# LowduinoPTH_Take2.net
KiCad netlist of a schematic drawn in EAGLE
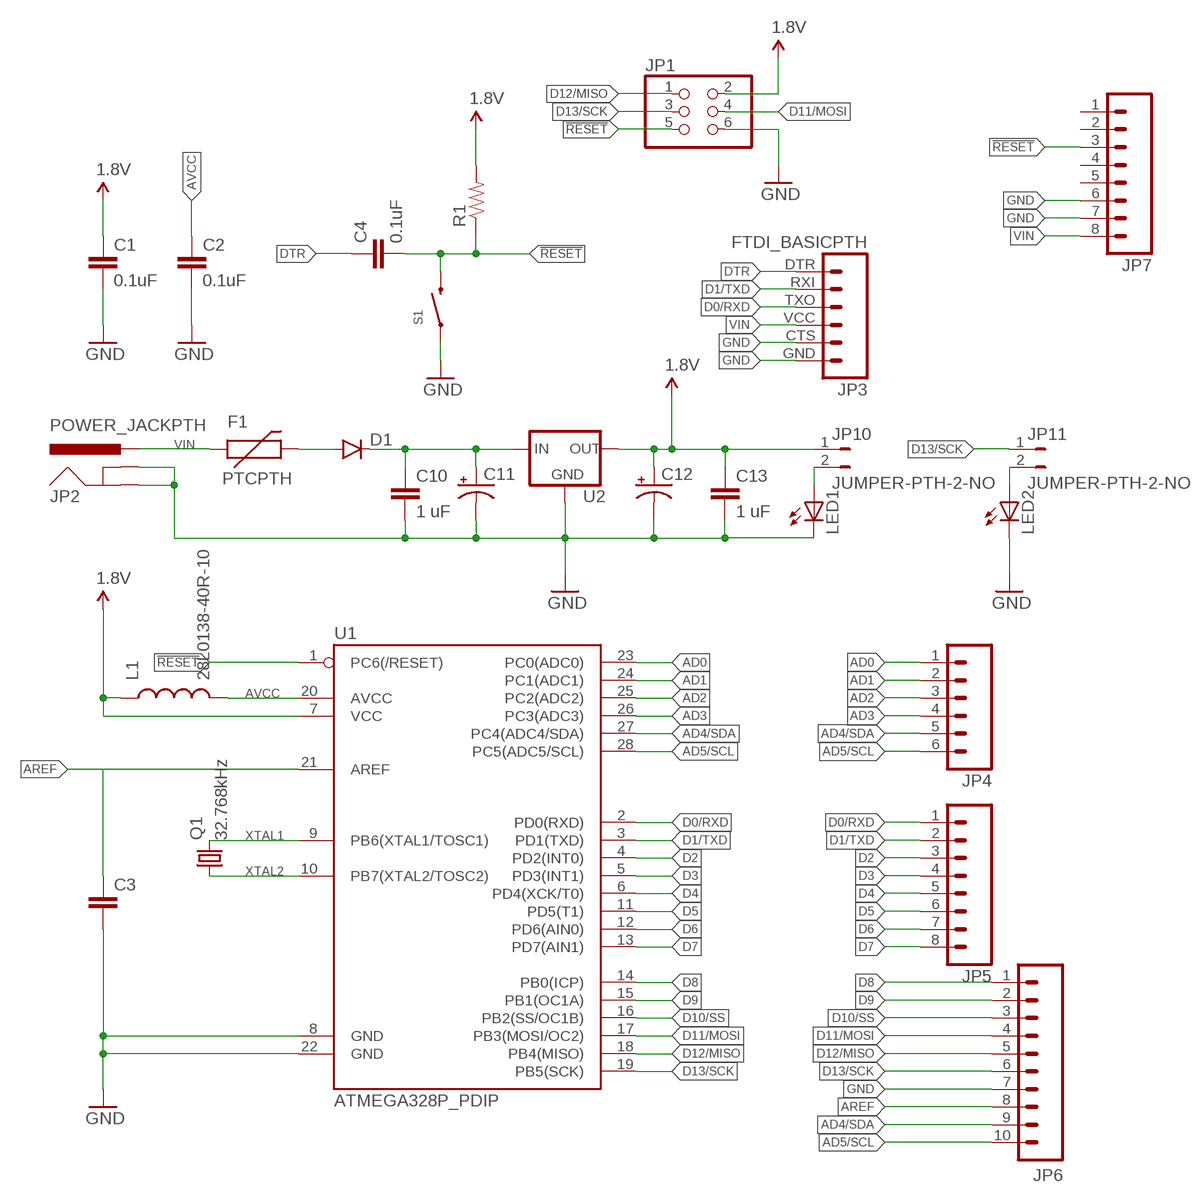
[diagram p0: schematic, sheet 1]

(export (version "E")
  (design (tool "Eeschema 10.0.6"))
  (components
    (comp (ref "C1")
      (value "0.1uF")
      (footprint "eagle-import:CAP-PTH-SMALL2")
      (libsource (lib "eagle-import") (part "CAPPTH2"))
    )
    (comp (ref "C2")
      (value "0.1uF")
      (footprint "eagle-import:CAP-PTH-5MM")
      (libsource (lib "eagle-import") (part "SparkFun-Passives_CAPPTH1"))
    )
    (comp (ref "C3")
      (value "CAPPTH2")
      (footprint "eagle-import:CAP-PTH-SMALL2")
      (libsource (lib "eagle-import") (part "CAPPTH2"))
    )
    (comp (ref "C4")
      (value "0.1uF")
      (footprint "eagle-import:CAP-PTH-SMALL2")
      (libsource (lib "eagle-import") (part "CAPPTH2"))
    )
    (comp (ref "C10")
      (value "1 uF")
      (footprint "eagle-import:CAP-PTH-SMALL2")
      (libsource (lib "eagle-import") (part "CAPPTH2"))
    )
    (comp (ref "C11")
      (value "CPOL-USE2.5-6")
      (footprint "eagle-import:E2,5-6")
      (libsource (lib "eagle-import") (part "CPOL-USE2.5-6"))
    )
    (comp (ref "C12")
      (value "CPOL-USE2.5-6")
      (footprint "eagle-import:E2,5-6")
      (libsource (lib "eagle-import") (part "CPOL-USE2.5-6"))
    )
    (comp (ref "C13")
      (value "1 uF")
      (footprint "eagle-import:CAP-PTH-SMALL2")
      (libsource (lib "eagle-import") (part "CAPPTH2"))
    )
    (comp (ref "D1")
      (value "DIODEPTH")
      (footprint "eagle-import:DIODE-1N4001")
      (libsource (lib "eagle-import") (part "DIODEPTH"))
    )
    (comp (ref "F1")
      (value "PTCPTH")
      (footprint "eagle-import:PTC")
      (libsource (lib "eagle-import") (part "PTCPTH"))
    )
    (comp (ref "JP1")
      (value "PINHD-2X3")
      (footprint "eagle-import:2X03")
      (libsource (lib "eagle-import") (part "PINHD-2X3"))
    )
    (comp (ref "JP2")
      (value "POWER_JACKPTH")
      (footprint "eagle-import:POWER_JACK_PTH")
      (libsource (lib "eagle-import") (part "POWER_JACKPTH"))
    )
    (comp (ref "JP3")
      (value "FTDI_BASICPTH")
      (footprint "eagle-import:FTDI_BASIC")
      (libsource (lib "eagle-import") (part "FTDI_BASICPTH"))
    )
    (comp (ref "JP4")
      (value "M06SILK_FEMALE_PTH")
      (footprint "eagle-import:1X06")
      (libsource (lib "eagle-import") (part "M06SILK_FEMALE_PTH"))
    )
    (comp (ref "JP5")
      (value "M08")
      (footprint "eagle-import:1X08_ROUND")
      (libsource (lib "eagle-import") (part "M08"))
    )
    (comp (ref "JP6")
      (value "M10SILK_FEMALE_PTH")
      (footprint "eagle-import:1X10")
      (libsource (lib "eagle-import") (part "M10SILK_FEMALE_PTH"))
    )
    (comp (ref "JP7")
      (value "M08")
      (footprint "eagle-import:1X08_ROUND")
      (libsource (lib "eagle-import") (part "M08"))
    )
    (comp (ref "JP10")
      (value "JUMPER-PTH-2-NO")
      (footprint "eagle-import:PTH-JUMPER-2-NO_NO_SILK")
      (libsource (lib "eagle-import") (part "JUMPER-PTH-2-NO"))
    )
    (comp (ref "JP11")
      (value "JUMPER-PTH-2-NO")
      (footprint "eagle-import:PTH-JUMPER-2-NO_NO_SILK")
      (libsource (lib "eagle-import") (part "JUMPER-PTH-2-NO"))
    )
    (comp (ref "L1")
      (value "28L0138-40R-10")
      (footprint "eagle-import:AXIAL-0.6")
      (libsource (lib "eagle-import") (part "INDUCTORAXIAL-0.6"))
    )
    (comp (ref "LED1")
      (value "LED3MM")
      (footprint "eagle-import:LED3MM")
      (libsource (lib "eagle-import") (part "LED3MM"))
    )
    (comp (ref "LED2")
      (value "LED3MM")
      (footprint "eagle-import:LED3MM")
      (libsource (lib "eagle-import") (part "LED3MM"))
    )
    (comp (ref "Q1")
      (value "32.768kHz")
      (footprint "eagle-import:TC26H")
      (libsource (lib "eagle-import") (part "CRYSTALTC26H"))
    )
    (comp (ref "R1")
      (value "RESISTORPTH-1/4W-VERT")
      (footprint "eagle-import:AXIAL-0.1")
      (libsource (lib "eagle-import") (part "RESISTORPTH-1/4W-VERT"))
    )
    (comp (ref "S1")
      (value "SWITCH-MOMENTARY-2PTH")
      (footprint "eagle-import:TACTILE-PTH")
      (libsource (lib "eagle-import") (part "SWITCH-MOMENTARY-2PTH"))
    )
    (comp (ref "U1")
      (value "ATMEGA328P_PDIP")
      (footprint "eagle-import:DIL28-3")
      (libsource (lib "eagle-import") (part "ATMEGA328P_PDIP"))
    )
    (comp (ref "U2")
      (value "V_REG_78XXTO-92_UNTESTED")
      (footprint "eagle-import:TO-92")
      (libsource (lib "eagle-import") (part "V_REG_78XXTO-92_UNTESTED"))
    )
  )
  (nets
    (net (code "1") (name "/XTAL1") (class "Default")
      (node (ref "Q1") (pin "2") (pinfunction "2_2") (pintype "passive"))
      (node (ref "U1") (pin "9") (pinfunction "PB6(XTAL1/TOSC1)_9") (pintype "bidirectional"))
    )
    (net (code "2") (name "/XTAL2") (class "Default")
      (node (ref "Q1") (pin "1") (pinfunction "1_1") (pintype "passive"))
      (node (ref "U1") (pin "10") (pinfunction "PB7(XTAL2/TOSC2)_10") (pintype "bidirectional"))
    )
    (net (code "3") (name "/~{RESET}") (class "Default")
      (node (ref "C4") (pin "2") (pinfunction "2_2") (pintype "passive"))
      (node (ref "JP1") (pin "5") (pinfunction "5_5") (pintype "passive"))
      (node (ref "JP7") (pin "3") (pinfunction "3_3") (pintype "passive"))
      (node (ref "R1") (pin "P$1") (pinfunction "1_P$1") (pintype "passive"))
      (node (ref "S1") (pin "3") (pinfunction "2_3") (pintype "passive"))
      (node (ref "U1") (pin "1") (pinfunction "PC6(/RESET)_1") (pintype "bidirectional"))
    )
    (net (code "4") (name "1.8V") (class "Default")
      (node (ref "C1") (pin "1") (pinfunction "1_1") (pintype "passive"))
      (node (ref "C12") (pin "+") (pinfunction "+_+") (pintype "passive"))
      (node (ref "C13") (pin "1") (pinfunction "1_1") (pintype "passive"))
      (node (ref "JP1") (pin "2") (pinfunction "2_2") (pintype "passive"))
      (node (ref "JP10") (pin "1") (pinfunction "1_1") (pintype "passive"))
      (node (ref "L1") (pin "P$1") (pinfunction "1_P$1") (pintype "passive"))
      (node (ref "R1") (pin "P$2") (pinfunction "2_P$2") (pintype "passive"))
      (node (ref "U1") (pin "7") (pinfunction "VCC_7") (pintype "bidirectional"))
      (node (ref "U2") (pin "3") (pinfunction "OUT_3") (pintype "output"))
    )
    (net (code "5") (name "AD0") (class "Default")
      (node (ref "JP4") (pin "1") (pinfunction "1_1") (pintype "passive"))
      (node (ref "U1") (pin "23") (pinfunction "PC0(ADC0)_23") (pintype "bidirectional"))
    )
    (net (code "6") (name "AD1") (class "Default")
      (node (ref "JP4") (pin "2") (pinfunction "2_2") (pintype "passive"))
      (node (ref "U1") (pin "24") (pinfunction "PC1(ADC1)_24") (pintype "bidirectional"))
    )
    (net (code "7") (name "AD2") (class "Default")
      (node (ref "JP4") (pin "3") (pinfunction "3_3") (pintype "passive"))
      (node (ref "U1") (pin "25") (pinfunction "PC2(ADC2)_25") (pintype "bidirectional"))
    )
    (net (code "8") (name "AD3") (class "Default")
      (node (ref "JP4") (pin "4") (pinfunction "4_4") (pintype "passive"))
      (node (ref "U1") (pin "26") (pinfunction "PC3(ADC3)_26") (pintype "bidirectional"))
    )
    (net (code "9") (name "AD4{slash}SDA") (class "Default")
      (node (ref "JP4") (pin "5") (pinfunction "5_5") (pintype "passive"))
      (node (ref "JP6") (pin "9") (pinfunction "9_9") (pintype "passive"))
      (node (ref "U1") (pin "27") (pinfunction "PC4(ADC4/SDA)_27") (pintype "bidirectional"))
    )
    (net (code "10") (name "AD5{slash}SCL") (class "Default")
      (node (ref "JP4") (pin "6") (pinfunction "6_6") (pintype "passive"))
      (node (ref "JP6") (pin "10") (pinfunction "10_10") (pintype "passive"))
      (node (ref "U1") (pin "28") (pinfunction "PC5(ADC5/SCL)_28") (pintype "bidirectional"))
    )
    (net (code "11") (name "AREF") (class "Default")
      (node (ref "C3") (pin "1") (pinfunction "1_1") (pintype "passive"))
      (node (ref "JP6") (pin "8") (pinfunction "8_8") (pintype "passive"))
      (node (ref "U1") (pin "21") (pinfunction "AREF_21") (pintype "bidirectional"))
    )
    (net (code "12") (name "AVCC") (class "Default")
      (node (ref "C2") (pin "1") (pinfunction "1_1") (pintype "passive"))
      (node (ref "L1") (pin "P$2") (pinfunction "2_P$2") (pintype "passive"))
      (node (ref "U1") (pin "20") (pinfunction "AVCC_20") (pintype "bidirectional"))
    )
    (net (code "13") (name "D0{slash}RXD") (class "Default")
      (node (ref "JP3") (pin "TXO") (pinfunction "3_TXO") (pintype "passive"))
      (node (ref "JP5") (pin "1") (pinfunction "1_1") (pintype "passive"))
      (node (ref "U1") (pin "2") (pinfunction "PD0(RXD)_2") (pintype "bidirectional"))
    )
    (net (code "14") (name "D1{slash}TXD") (class "Default")
      (node (ref "JP3") (pin "RXI") (pinfunction "2_RXI") (pintype "passive"))
      (node (ref "JP5") (pin "2") (pinfunction "2_2") (pintype "passive"))
      (node (ref "U1") (pin "3") (pinfunction "PD1(TXD)_3") (pintype "bidirectional"))
    )
    (net (code "15") (name "D2") (class "Default")
      (node (ref "JP5") (pin "3") (pinfunction "3_3") (pintype "passive"))
      (node (ref "U1") (pin "4") (pinfunction "PD2(INT0)_4") (pintype "bidirectional"))
    )
    (net (code "16") (name "D3") (class "Default")
      (node (ref "JP5") (pin "4") (pinfunction "4_4") (pintype "passive"))
      (node (ref "U1") (pin "5") (pinfunction "PD3(INT1)_5") (pintype "bidirectional"))
    )
    (net (code "17") (name "D4") (class "Default")
      (node (ref "JP5") (pin "5") (pinfunction "5_5") (pintype "passive"))
      (node (ref "U1") (pin "6") (pinfunction "PD4(XCK/T0)_6") (pintype "bidirectional"))
    )
    (net (code "18") (name "D5") (class "Default")
      (node (ref "JP5") (pin "6") (pinfunction "6_6") (pintype "passive"))
      (node (ref "U1") (pin "11") (pinfunction "PD5(T1)_11") (pintype "bidirectional"))
    )
    (net (code "19") (name "D6") (class "Default")
      (node (ref "JP5") (pin "7") (pinfunction "7_7") (pintype "passive"))
      (node (ref "U1") (pin "12") (pinfunction "PD6(AIN0)_12") (pintype "bidirectional"))
    )
    (net (code "20") (name "D7") (class "Default")
      (node (ref "JP5") (pin "8") (pinfunction "8_8") (pintype "passive"))
      (node (ref "U1") (pin "13") (pinfunction "PD7(AIN1)_13") (pintype "bidirectional"))
    )
    (net (code "21") (name "D8") (class "Default")
      (node (ref "JP6") (pin "1") (pinfunction "1_1") (pintype "passive"))
      (node (ref "U1") (pin "14") (pinfunction "PB0(ICP)_14") (pintype "bidirectional"))
    )
    (net (code "22") (name "D9") (class "Default")
      (node (ref "JP6") (pin "2") (pinfunction "2_2") (pintype "passive"))
      (node (ref "U1") (pin "15") (pinfunction "PB1(OC1A)_15") (pintype "bidirectional"))
    )
    (net (code "23") (name "D10{slash}SS") (class "Default")
      (node (ref "JP6") (pin "3") (pinfunction "3_3") (pintype "passive"))
      (node (ref "U1") (pin "16") (pinfunction "PB2(SS/OC1B)_16") (pintype "bidirectional"))
    )
    (net (code "24") (name "D11{slash}MOSI") (class "Default")
      (node (ref "JP1") (pin "4") (pinfunction "4_4") (pintype "passive"))
      (node (ref "JP6") (pin "4") (pinfunction "4_4") (pintype "passive"))
      (node (ref "U1") (pin "17") (pinfunction "PB3(MOSI/OC2)_17") (pintype "bidirectional"))
    )
    (net (code "25") (name "D12{slash}MISO") (class "Default")
      (node (ref "JP1") (pin "1") (pinfunction "1_1") (pintype "passive"))
      (node (ref "JP6") (pin "5") (pinfunction "5_5") (pintype "passive"))
      (node (ref "U1") (pin "18") (pinfunction "PB4(MISO)_18") (pintype "bidirectional"))
    )
    (net (code "26") (name "D13{slash}SCK") (class "Default")
      (node (ref "JP1") (pin "3") (pinfunction "3_3") (pintype "passive"))
      (node (ref "JP11") (pin "1") (pinfunction "1_1") (pintype "passive"))
      (node (ref "JP6") (pin "6") (pinfunction "6_6") (pintype "passive"))
      (node (ref "U1") (pin "19") (pinfunction "PB5(SCK)_19") (pintype "bidirectional"))
    )
    (net (code "27") (name "DTR") (class "Default")
      (node (ref "C4") (pin "1") (pinfunction "1_1") (pintype "passive"))
      (node (ref "JP3") (pin "DTR") (pinfunction "1_DTR") (pintype "passive"))
    )
    (net (code "28") (name "GND") (class "Default")
      (node (ref "C1") (pin "2") (pinfunction "2_2") (pintype "passive"))
      (node (ref "C10") (pin "2") (pinfunction "2_2") (pintype "passive"))
      (node (ref "C11") (pin "-") (pinfunction "-_-") (pintype "passive"))
      (node (ref "C12") (pin "-") (pinfunction "-_-") (pintype "passive"))
      (node (ref "C13") (pin "2") (pinfunction "2_2") (pintype "passive"))
      (node (ref "C2") (pin "2") (pinfunction "2_2") (pintype "passive"))
      (node (ref "C3") (pin "2") (pinfunction "2_2") (pintype "passive"))
      (node (ref "JP1") (pin "6") (pinfunction "6_6") (pintype "passive"))
      (node (ref "JP2") (pin "GND") (pinfunction "GND_GND") (pintype "bidirectional"))
      (node (ref "JP2") (pin "GNDBREAK") (pinfunction "GNDBREAK_GNDBREAK") (pintype "bidirectional"))
      (node (ref "JP3") (pin "CTS") (pinfunction "5_CTS") (pintype "passive"))
      (node (ref "JP3") (pin "GND") (pinfunction "6_GND") (pintype "passive"))
      (node (ref "JP6") (pin "7") (pinfunction "7_7") (pintype "passive"))
      (node (ref "JP7") (pin "6") (pinfunction "6_6") (pintype "passive"))
      (node (ref "JP7") (pin "7") (pinfunction "7_7") (pintype "passive"))
      (node (ref "LED1") (pin "K") (pinfunction "C_K") (pintype "passive"))
      (node (ref "LED2") (pin "K") (pinfunction "C_K") (pintype "passive"))
      (node (ref "S1") (pin "1") (pinfunction "1_1") (pintype "passive"))
      (node (ref "U1") (pin "22") (pinfunction "GND_22") (pintype "bidirectional"))
      (node (ref "U1") (pin "8") (pinfunction "GND_8") (pintype "bidirectional"))
      (node (ref "U2") (pin "1") (pinfunction "GND_1") (pintype "input"))
    )
    (net (code "29") (name "Net-(F1-2)") (class "Default")
      (node (ref "D1") (pin "A") (pinfunction "A_A") (pintype "passive"))
      (node (ref "F1") (pin "P$2") (pinfunction "2_P$2") (pintype "bidirectional"))
    )
    (net (code "30") (name "Net-(JP10-Pad2)") (class "Default")
      (node (ref "JP10") (pin "2") (pinfunction "2_2") (pintype "passive"))
      (node (ref "LED1") (pin "A") (pinfunction "A_A") (pintype "passive"))
    )
    (net (code "31") (name "Net-(JP11-Pad2)") (class "Default")
      (node (ref "JP11") (pin "2") (pinfunction "2_2") (pintype "passive"))
      (node (ref "LED2") (pin "A") (pinfunction "A_A") (pintype "passive"))
    )
    (net (code "32") (name "Net-(U2-IN)") (class "Default")
      (node (ref "C10") (pin "1") (pinfunction "1_1") (pintype "passive"))
      (node (ref "C11") (pin "+") (pinfunction "+_+") (pintype "passive"))
      (node (ref "D1") (pin "C") (pinfunction "C_C") (pintype "passive"))
      (node (ref "U2") (pin "2") (pinfunction "IN_2") (pintype "input"))
    )
    (net (code "33") (name "VIN") (class "Default")
      (node (ref "F1") (pin "P$1") (pinfunction "1_P$1") (pintype "bidirectional"))
      (node (ref "JP2") (pin "PWR") (pinfunction "PWR_PWR") (pintype "bidirectional"))
      (node (ref "JP3") (pin "VCC") (pinfunction "4_VCC") (pintype "passive"))
      (node (ref "JP7") (pin "8") (pinfunction "8_8") (pintype "passive"))
    )
    (net (code "34") (name "unconnected-(JP7-Pad1)") (class "Default")
      (node (ref "JP7") (pin "1") (pinfunction "1_1") (pintype "passive"))
    )
    (net (code "35") (name "unconnected-(JP7-Pad2)") (class "Default")
      (node (ref "JP7") (pin "2") (pinfunction "2_2") (pintype "passive"))
    )
    (net (code "36") (name "unconnected-(JP7-Pad4)") (class "Default")
      (node (ref "JP7") (pin "4") (pinfunction "4_4") (pintype "passive"))
    )
    (net (code "37") (name "unconnected-(JP7-Pad5)") (class "Default")
      (node (ref "JP7") (pin "5") (pinfunction "5_5") (pintype "passive"))
    )
  )
)
